# TeensyView.net
KiCad netlist of a schematic drawn in EAGLE
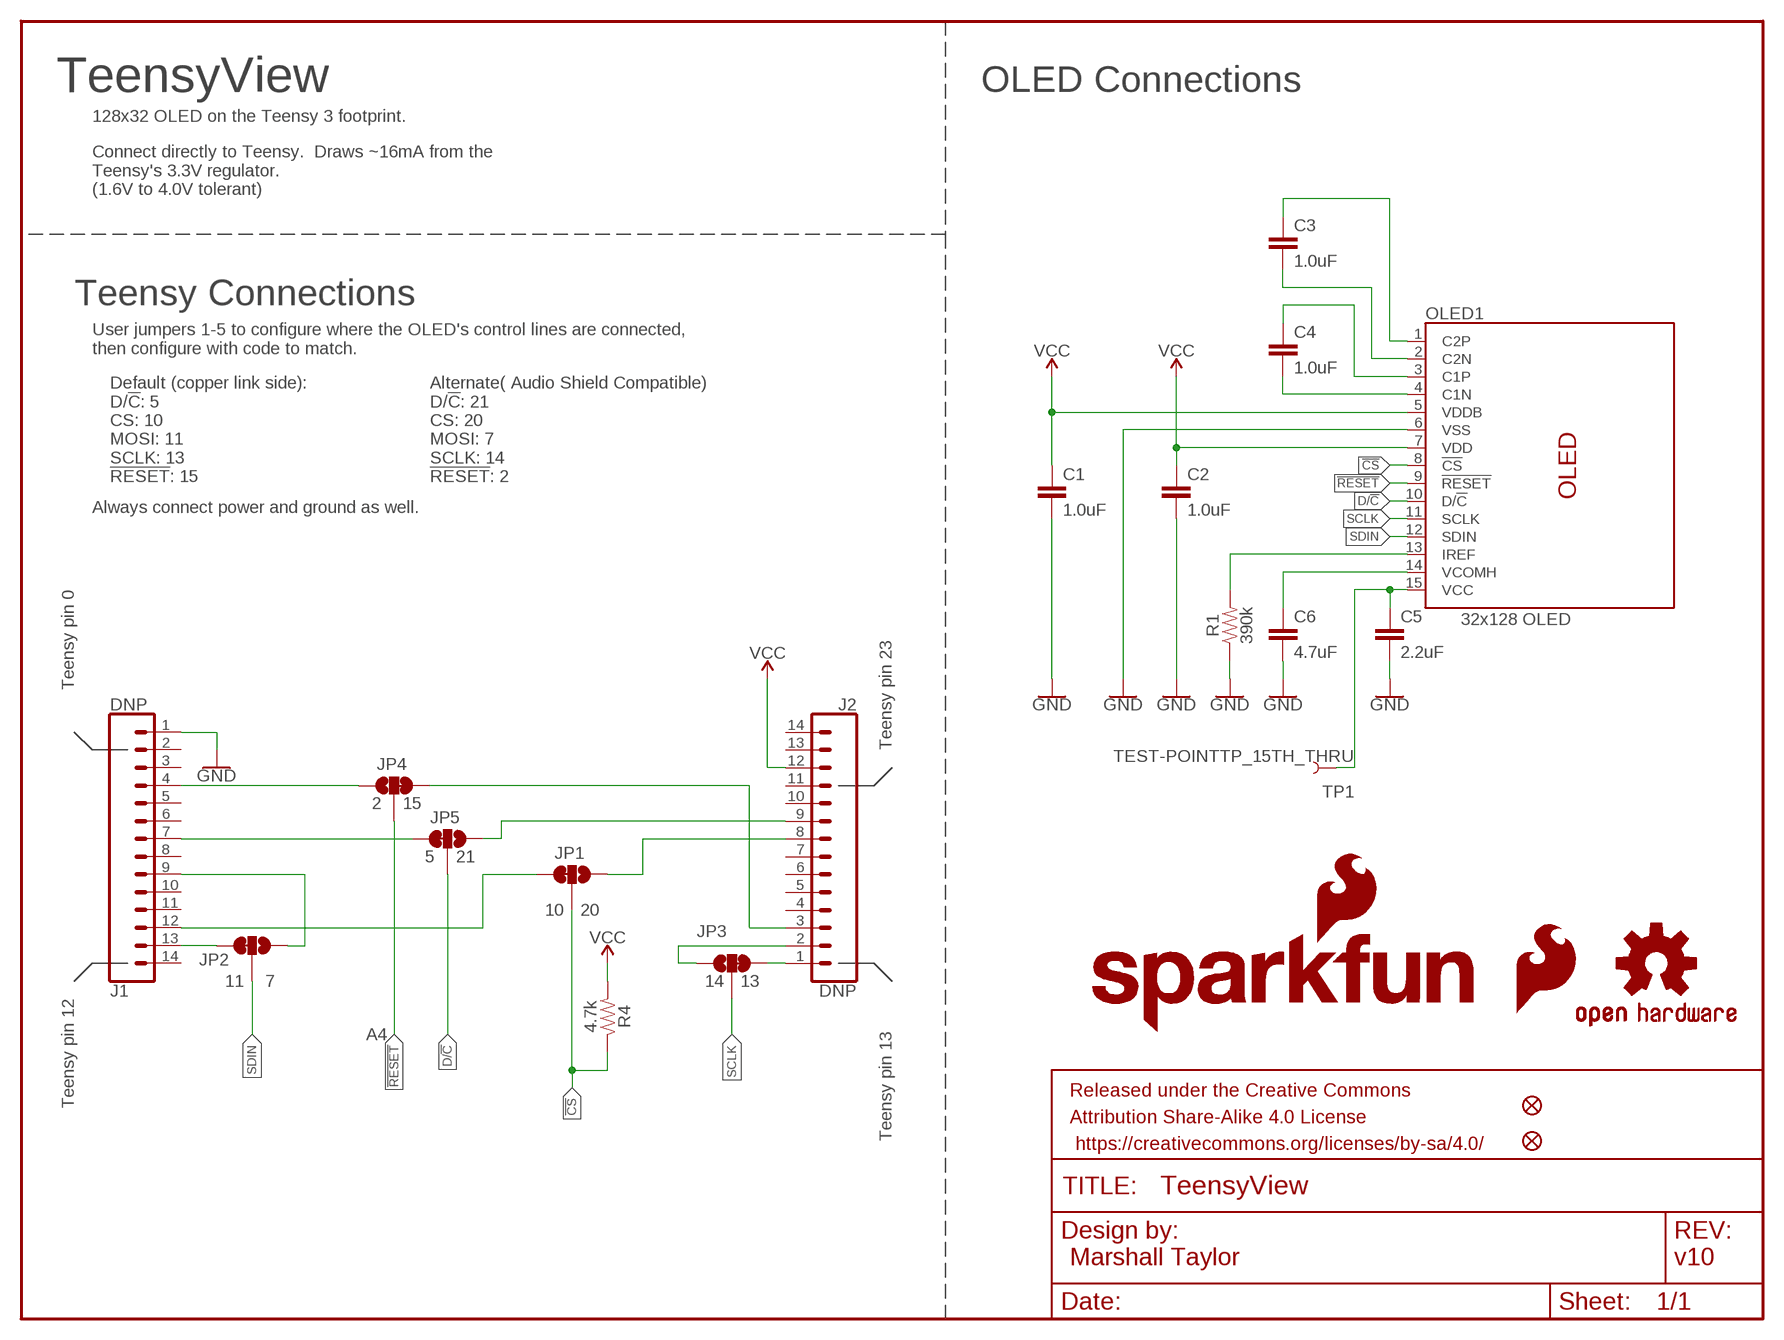
[diagram p0: schematic, sheet 1]

(export (version "E")
  (design (tool "Eeschema 10.0.6"))
  (components
    (comp (ref "C1")
      (value "1.0uF")
      (footprint "eagle-import:0402")
      (libsource (lib "eagle-import") (part "1.0UF-0402-16V-10%"))
    )
    (comp (ref "C2")
      (value "1.0uF")
      (footprint "eagle-import:0402")
      (libsource (lib "eagle-import") (part "1.0UF-0402-16V-10%"))
    )
    (comp (ref "C3")
      (value "1.0uF")
      (footprint "eagle-import:0402")
      (libsource (lib "eagle-import") (part "1.0UF-0402-16V-10%"))
    )
    (comp (ref "C4")
      (value "1.0uF")
      (footprint "eagle-import:0402")
      (libsource (lib "eagle-import") (part "1.0UF-0402-16V-10%"))
    )
    (comp (ref "C5")
      (value "2.2uF")
      (footprint "eagle-import:0805")
      (libsource (lib "eagle-import") (part "2.2UF-0805-25V-(+80/-20%)"))
    )
    (comp (ref "C6")
      (value "4.7uF")
      (footprint "eagle-import:1206")
      (fields (field (name "PROD_ID") "CAP-10300"))
      (libsource (lib "eagle-import") (part "4.7UF-1206-16V-(+80/-20%)"))
    )
    (comp (ref "FD1")
      (value "FIDUCIALUFIDUCIAL")
      (footprint "eagle-import:FIDUCIAL-MICRO")
      (libsource (lib "eagle-import") (part "FIDUCIALUFIDUCIAL"))
    )
    (comp (ref "FD2")
      (value "FIDUCIALUFIDUCIAL")
      (footprint "eagle-import:FIDUCIAL-MICRO")
      (libsource (lib "eagle-import") (part "FIDUCIALUFIDUCIAL"))
    )
    (comp (ref "FRAME1")
      (value "FRAME-LETTER")
      (footprint "eagle-import:CREATIVE_COMMONS")
      (libsource (lib "eagle-import") (part "FRAME-LETTER"))
    )
    (comp (ref "J1")
      (value "DNP")
      (footprint "eagle-import:1X14_NO_SILK")
      (libsource (lib "eagle-import") (part "CONN_14NO_SILK"))
    )
    (comp (ref "J2")
      (value "DNP")
      (footprint "eagle-import:1X14_NO_SILK")
      (libsource (lib "eagle-import") (part "CONN_14NO_SILK"))
    )
    (comp (ref "JP1")
      (value "JUMPER-SMT_3_1-NC_TRACE_SILK")
      (footprint "eagle-import:SMT-JUMPER_3_1-NC_TRACE_SILK")
      (libsource (lib "eagle-import") (part "JUMPER-SMT_3_1-NC_TRACE_SILK"))
    )
    (comp (ref "JP2")
      (value "JUMPER-SMT_3_1-NC_TRACE_SILK")
      (footprint "eagle-import:SMT-JUMPER_3_1-NC_TRACE_SILK")
      (libsource (lib "eagle-import") (part "JUMPER-SMT_3_1-NC_TRACE_SILK"))
    )
    (comp (ref "JP3")
      (value "JUMPER-SMT_3_1-NC_TRACE_SILK")
      (footprint "eagle-import:SMT-JUMPER_3_1-NC_TRACE_SILK")
      (libsource (lib "eagle-import") (part "JUMPER-SMT_3_1-NC_TRACE_SILK"))
    )
    (comp (ref "JP4")
      (value "JUMPER-SMT_3_1-NC_TRACE_SILK")
      (footprint "eagle-import:SMT-JUMPER_3_1-NC_TRACE_SILK")
      (libsource (lib "eagle-import") (part "JUMPER-SMT_3_1-NC_TRACE_SILK"))
    )
    (comp (ref "JP5")
      (value "JUMPER-SMT_3_1-NC_TRACE_SILK")
      (footprint "eagle-import:SMT-JUMPER_3_1-NC_TRACE_SILK")
      (libsource (lib "eagle-import") (part "JUMPER-SMT_3_1-NC_TRACE_SILK"))
    )
    (comp (ref "LOGO1")
      (value "SFE_LOGO_FLAME.1_INCH")
      (footprint "eagle-import:SFE_LOGO_FLAME_.1")
      (libsource (lib "eagle-import") (part "SFE_LOGO_FLAME.1_INCH"))
    )
    (comp (ref "LOGO2")
      (value "OSHW-LOGOS")
      (footprint "eagle-import:OSHW-LOGO-S")
      (libsource (lib "eagle-import") (part "OSHW-LOGOS"))
    )
    (comp (ref "LOGO3")
      (value "SFE_LOGO_NAME_FLAME.1_INCH")
      (footprint "eagle-import:SFE_LOGO_NAME_FLAME_.1")
      (libsource (lib "eagle-import") (part "SFE_LOGO_NAME_FLAME.1_INCH"))
    )
    (comp (ref "OLED1")
      (value "32x128 OLED")
      (footprint "eagle-import:OLED-UG-2832TSWGG01-REAR")
      (libsource (lib "eagle-import") (part "OLED128X64SIDEREAR-MOUNT"))
    )
    (comp (ref "R1")
      (value "390k")
      (footprint "eagle-import:0603")
      (libsource (lib "eagle-import") (part "390KOHM-0603-1/10W-1%"))
    )
    (comp (ref "R4")
      (value "4.7k")
      (footprint "eagle-import:0603")
      (libsource (lib "eagle-import") (part "4.7KOHM-0603-1/10W-1%"))
    )
    (comp (ref "TP1")
      (value "TEST-POINTTP_15TH_THRU")
      (footprint "eagle-import:TP_15TH")
      (libsource (lib "eagle-import") (part "TEST-POINTTP_15TH_THRU"))
    )
  )
  (nets
    (net (code "1") (name "/D{slash}~{C}") (class "Default")
      (node (ref "JP5") (pin "2") (pinfunction "2_2") (pintype "passive"))
      (node (ref "OLED1") (pin "10") (pinfunction "D/~{C}_10") (pintype "bidirectional"))
    )
    (net (code "2") (name "/~{CS}") (class "Default")
      (node (ref "JP1") (pin "2") (pinfunction "2_2") (pintype "passive"))
      (node (ref "OLED1") (pin "8") (pinfunction "~{CS}_8") (pintype "bidirectional"))
      (node (ref "R4") (pin "1") (pinfunction "1_1") (pintype "passive"))
    )
    (net (code "3") (name "/~{RESET}") (class "Default")
      (node (ref "JP4") (pin "2") (pinfunction "2_2") (pintype "passive"))
      (node (ref "OLED1") (pin "9") (pinfunction "~{RESET}_9") (pintype "bidirectional"))
    )
    (net (code "4") (name "GND") (class "Default")
      (node (ref "C1") (pin "2") (pinfunction "2_2") (pintype "passive"))
      (node (ref "C2") (pin "2") (pinfunction "2_2") (pintype "passive"))
      (node (ref "C5") (pin "2") (pinfunction "2_2") (pintype "passive"))
      (node (ref "C6") (pin "2") (pinfunction "2_2") (pintype "passive"))
      (node (ref "J1") (pin "1") (pinfunction "1_1") (pintype "passive"))
      (node (ref "OLED1") (pin "6") (pinfunction "VSS_6") (pintype "bidirectional"))
      (node (ref "R1") (pin "1") (pinfunction "1_1") (pintype "passive"))
    )
    (net (code "5") (name "Net-(J1-Pad4)") (class "Default")
      (node (ref "J1") (pin "4") (pinfunction "4_4") (pintype "passive"))
      (node (ref "JP4") (pin "1") (pinfunction "1_1") (pintype "passive"))
    )
    (net (code "6") (name "Net-(J1-Pad7)") (class "Default")
      (node (ref "J1") (pin "7") (pinfunction "7_7") (pintype "passive"))
      (node (ref "JP5") (pin "3") (pinfunction "3_3") (pintype "passive"))
    )
    (net (code "7") (name "Net-(J1-Pad9)") (class "Default")
      (node (ref "J1") (pin "9") (pinfunction "9_9") (pintype "passive"))
      (node (ref "JP2") (pin "1") (pinfunction "1_1") (pintype "passive"))
    )
    (net (code "8") (name "Net-(J1-Pad12)") (class "Default")
      (node (ref "J1") (pin "12") (pinfunction "12_12") (pintype "passive"))
      (node (ref "JP1") (pin "3") (pinfunction "3_3") (pintype "passive"))
    )
    (net (code "9") (name "Net-(J1-Pad13)") (class "Default")
      (node (ref "J1") (pin "13") (pinfunction "13_13") (pintype "passive"))
      (node (ref "JP2") (pin "3") (pinfunction "3_3") (pintype "passive"))
    )
    (net (code "10") (name "Net-(J2-Pad1)") (class "Default")
      (node (ref "J2") (pin "1") (pinfunction "1_1") (pintype "passive"))
      (node (ref "JP3") (pin "3") (pinfunction "3_3") (pintype "passive"))
    )
    (net (code "11") (name "Net-(J2-Pad2)") (class "Default")
      (node (ref "J2") (pin "2") (pinfunction "2_2") (pintype "passive"))
      (node (ref "JP3") (pin "1") (pinfunction "1_1") (pintype "passive"))
    )
    (net (code "12") (name "Net-(J2-Pad3)") (class "Default")
      (node (ref "J2") (pin "3") (pinfunction "3_3") (pintype "passive"))
      (node (ref "JP4") (pin "3") (pinfunction "3_3") (pintype "passive"))
    )
    (net (code "13") (name "Net-(J2-Pad8)") (class "Default")
      (node (ref "J2") (pin "8") (pinfunction "8_8") (pintype "passive"))
      (node (ref "JP1") (pin "1") (pinfunction "1_1") (pintype "passive"))
    )
    (net (code "14") (name "Net-(J2-Pad9)") (class "Default")
      (node (ref "J2") (pin "9") (pinfunction "9_9") (pintype "passive"))
      (node (ref "JP5") (pin "1") (pinfunction "1_1") (pintype "passive"))
    )
    (net (code "15") (name "Net-(OLED1-C1N)") (class "Default")
      (node (ref "C4") (pin "2") (pinfunction "2_2") (pintype "passive"))
      (node (ref "OLED1") (pin "4") (pinfunction "C1N_4") (pintype "bidirectional"))
    )
    (net (code "16") (name "Net-(OLED1-C1P)") (class "Default")
      (node (ref "C4") (pin "1") (pinfunction "1_1") (pintype "passive"))
      (node (ref "OLED1") (pin "3") (pinfunction "C1P_3") (pintype "bidirectional"))
    )
    (net (code "17") (name "Net-(OLED1-C2N)") (class "Default")
      (node (ref "C3") (pin "2") (pinfunction "2_2") (pintype "passive"))
      (node (ref "OLED1") (pin "2") (pinfunction "C2N_2") (pintype "bidirectional"))
    )
    (net (code "18") (name "Net-(OLED1-C2P)") (class "Default")
      (node (ref "C3") (pin "1") (pinfunction "1_1") (pintype "passive"))
      (node (ref "OLED1") (pin "1") (pinfunction "C2P_1") (pintype "bidirectional"))
    )
    (net (code "19") (name "Net-(OLED1-IREF)") (class "Default")
      (node (ref "OLED1") (pin "13") (pinfunction "IREF_13") (pintype "bidirectional"))
      (node (ref "R1") (pin "2") (pinfunction "2_2") (pintype "passive"))
    )
    (net (code "20") (name "Net-(OLED1-VCC)") (class "Default")
      (node (ref "C5") (pin "1") (pinfunction "1_1") (pintype "passive"))
      (node (ref "OLED1") (pin "15") (pinfunction "VCC_15") (pintype "bidirectional"))
      (node (ref "TP1") (pin "P$1") (pinfunction "1_P$1") (pintype "bidirectional"))
    )
    (net (code "21") (name "Net-(OLED1-VCOMH)") (class "Default")
      (node (ref "C6") (pin "1") (pinfunction "1_1") (pintype "passive"))
      (node (ref "OLED1") (pin "14") (pinfunction "VCOMH_14") (pintype "bidirectional"))
    )
    (net (code "22") (name "SCLK") (class "Default")
      (node (ref "JP3") (pin "2") (pinfunction "2_2") (pintype "passive"))
      (node (ref "OLED1") (pin "11") (pinfunction "SCLK_11") (pintype "bidirectional"))
    )
    (net (code "23") (name "SDIN") (class "Default")
      (node (ref "JP2") (pin "2") (pinfunction "2_2") (pintype "passive"))
      (node (ref "OLED1") (pin "12") (pinfunction "SDIN_12") (pintype "bidirectional"))
    )
    (net (code "24") (name "VCC") (class "Default")
      (node (ref "C1") (pin "1") (pinfunction "1_1") (pintype "passive"))
      (node (ref "C2") (pin "1") (pinfunction "1_1") (pintype "passive"))
      (node (ref "J2") (pin "12") (pinfunction "12_12") (pintype "passive"))
      (node (ref "OLED1") (pin "5") (pinfunction "VDDB_5") (pintype "bidirectional"))
      (node (ref "OLED1") (pin "7") (pinfunction "VDD_7") (pintype "bidirectional"))
      (node (ref "R4") (pin "2") (pinfunction "2_2") (pintype "passive"))
    )
    (net (code "25") (name "unconnected-(J1-Pad2)") (class "Default")
      (node (ref "J1") (pin "2") (pinfunction "2_2") (pintype "passive"))
    )
    (net (code "26") (name "unconnected-(J1-Pad3)") (class "Default")
      (node (ref "J1") (pin "3") (pinfunction "3_3") (pintype "passive"))
    )
    (net (code "27") (name "unconnected-(J1-Pad5)") (class "Default")
      (node (ref "J1") (pin "5") (pinfunction "5_5") (pintype "passive"))
    )
    (net (code "28") (name "unconnected-(J1-Pad6)") (class "Default")
      (node (ref "J1") (pin "6") (pinfunction "6_6") (pintype "passive"))
    )
    (net (code "29") (name "unconnected-(J1-Pad8)") (class "Default")
      (node (ref "J1") (pin "8") (pinfunction "8_8") (pintype "passive"))
    )
    (net (code "30") (name "unconnected-(J1-Pad10)") (class "Default")
      (node (ref "J1") (pin "10") (pinfunction "10_10") (pintype "passive"))
    )
    (net (code "31") (name "unconnected-(J1-Pad11)") (class "Default")
      (node (ref "J1") (pin "11") (pinfunction "11_11") (pintype "passive"))
    )
    (net (code "32") (name "unconnected-(J1-Pad14)") (class "Default")
      (node (ref "J1") (pin "14") (pinfunction "14_14") (pintype "passive"))
    )
    (net (code "33") (name "unconnected-(J2-Pad4)") (class "Default")
      (node (ref "J2") (pin "4") (pinfunction "4_4") (pintype "passive"))
    )
    (net (code "34") (name "unconnected-(J2-Pad5)") (class "Default")
      (node (ref "J2") (pin "5") (pinfunction "5_5") (pintype "passive"))
    )
    (net (code "35") (name "unconnected-(J2-Pad6)") (class "Default")
      (node (ref "J2") (pin "6") (pinfunction "6_6") (pintype "passive"))
    )
    (net (code "36") (name "unconnected-(J2-Pad7)") (class "Default")
      (node (ref "J2") (pin "7") (pinfunction "7_7") (pintype "passive"))
    )
    (net (code "37") (name "unconnected-(J2-Pad10)") (class "Default")
      (node (ref "J2") (pin "10") (pinfunction "10_10") (pintype "passive"))
    )
    (net (code "38") (name "unconnected-(J2-Pad11)") (class "Default")
      (node (ref "J2") (pin "11") (pinfunction "11_11") (pintype "passive"))
    )
    (net (code "39") (name "unconnected-(J2-Pad13)") (class "Default")
      (node (ref "J2") (pin "13") (pinfunction "13_13") (pintype "passive"))
    )
    (net (code "40") (name "unconnected-(J2-Pad14)") (class "Default")
      (node (ref "J2") (pin "14") (pinfunction "14_14") (pintype "passive"))
    )
  )
)
